# CAN.net
KiCad netlist of a schematic drawn in Altium Designer
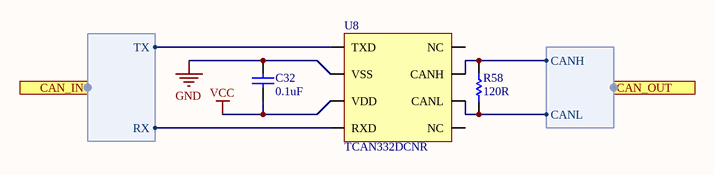
[diagram p0: CAN.SchDoc]

(export (version "E")
  (design (tool "Eeschema 10.0.6"))
  (components
    (comp (ref "C32")
      (value "0.1uF")
      (footprint "C0603[1608X92]")
      (description "0.1uF 6.3V 10% 0603 (1608 Metric)")
      (fields (field (name "PARTNUMBER") "GRM188R70J104KA01D") (field (name "MANUFACTURER") "Murata"))
      (libsource (lib "Capacitors") (part "CAP_0.1uF_6.3V_0603_10%"))
    )
    (comp (ref "R58")
      (value "120R")
      (footprint "R0603[1608]")
      (description "120R 0.25W 1% 0603 (1005 Metric)")
      (fields (field (name "MANUFACTURER") "Vishay / Dale") (field (name "PARTNUMBER") "CRCW0603120RFKEAHP"))
      (libsource (lib "Resistors") (part "RES_120R_0603_1%"))
    )
    (comp (ref "U8")
      (value "TCAN332DCNR")
      (footprint "SOT-23-8")
      (description "CAN Interface IC 3.3-V CAN Transceivers with CAN FD (Flexible Data Rate) 8-SOT-23 -40 to 125")
      (fields (field (name "MANUFACTURER") "Texas Instruments"))
      (libsource (lib "ICs") (part "TCAN332DCNR"))
    )
  )
  (nets
    (net (code "4") (name "/CANH") (class "Default")
      (node (ref "R58") (pin "2") (pinfunction "2_2") (pintype "passive"))
      (node (ref "U8") (pin "7") (pinfunction "CANH_7") (pintype "passive"))
    )
    (net (code "5") (name "/CANL") (class "Default")
      (node (ref "R58") (pin "1") (pinfunction "1_1") (pintype "passive"))
      (node (ref "U8") (pin "6") (pinfunction "CANL_6") (pintype "passive"))
    )
    (net (code "6") (name "/RX") (class "Default")
      (node (ref "U8") (pin "4") (pinfunction "RXD_4") (pintype "passive"))
    )
    (net (code "7") (name "/TX") (class "Default")
      (node (ref "U8") (pin "1") (pinfunction "TXD_1") (pintype "passive"))
    )
    (net (code "10") (name "GND") (class "Default")
      (node (ref "C32") (pin "2") (pinfunction "2_2") (pintype "passive"))
      (node (ref "U8") (pin "2") (pinfunction "VSS_2") (pintype "passive"))
    )
    (net (code "11") (name "VCC") (class "Default")
      (node (ref "C32") (pin "1") (pinfunction "1_1") (pintype "passive"))
      (node (ref "U8") (pin "3") (pinfunction "VDD_3") (pintype "passive"))
    )
    (net (code "12") (name "unconnected-(U8-NC-Pad5)") (class "Default")
      (node (ref "U8") (pin "5") (pinfunction "NC_5") (pintype "passive"))
    )
    (net (code "13") (name "unconnected-(U8-NC-Pad8)") (class "Default")
      (node (ref "U8") (pin "8") (pinfunction "NC_8") (pintype "passive"))
    )
  )
)
